# Boczek_schm_pls_check.net
KiCad netlist of a schematic drawn in EAGLE
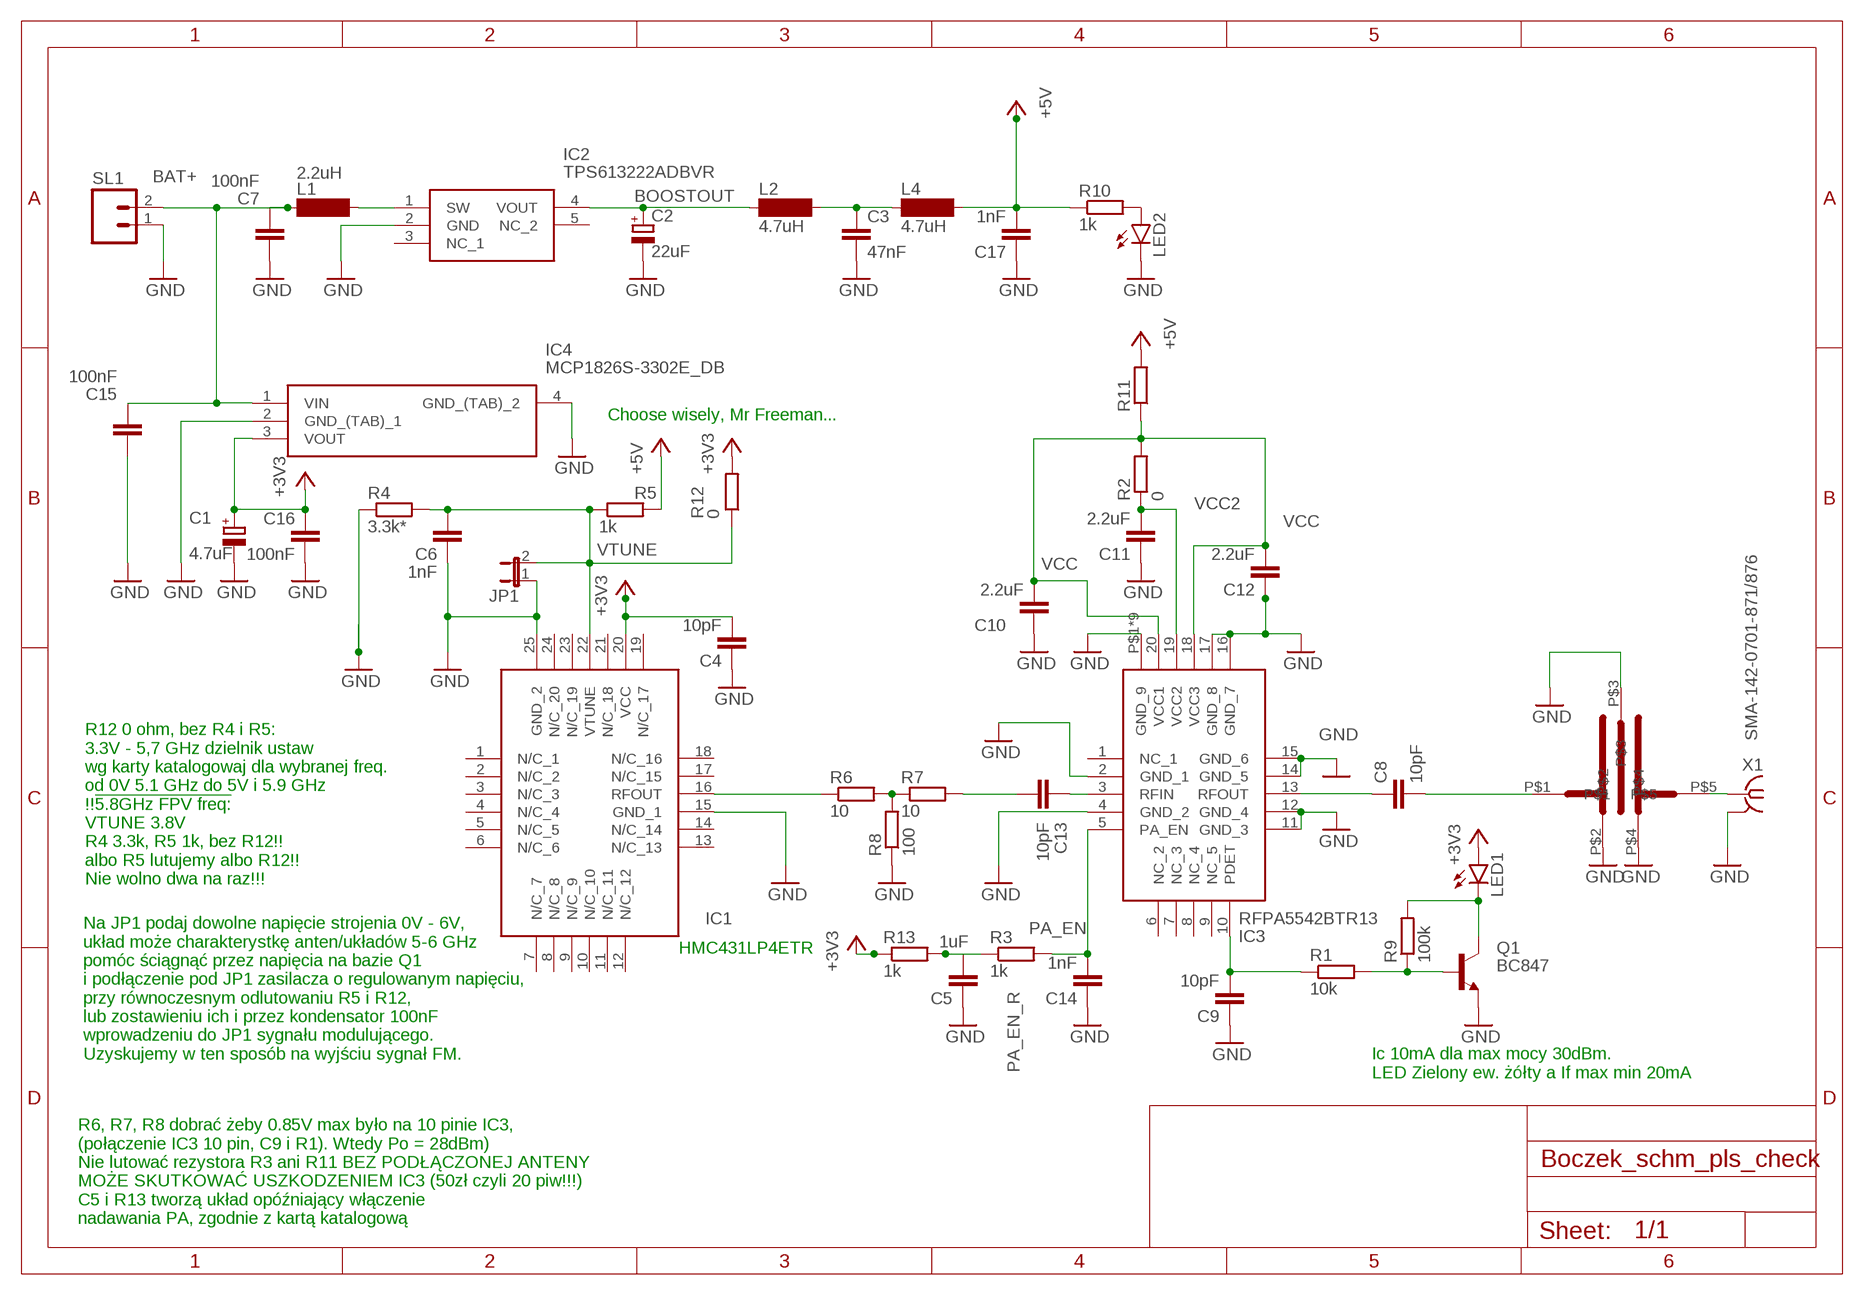
[diagram p0: schematic, sheet 1]

(export (version "E")
  (design (tool "Eeschema 10.0.6"))
  (components
    (comp (ref "C1")
      (value "4.7uF")
      (footprint "eagle-import:SMC_E")
      (libsource (lib "eagle-import") (part "CPOL-EUSMCE"))
    )
    (comp (ref "C2")
      (value "22uF")
      (footprint "eagle-import:SMC_E")
      (libsource (lib "eagle-import") (part "CPOL-EUSMCE"))
    )
    (comp (ref "C3")
      (value "47nF")
      (footprint "eagle-import:C1206")
      (libsource (lib "eagle-import") (part "C-EUC1206"))
    )
    (comp (ref "C4")
      (value "10pF")
      (footprint "eagle-import:C0603")
      (libsource (lib "eagle-import") (part "C-EUC0603"))
    )
    (comp (ref "C5")
      (value "1uF")
      (footprint "eagle-import:C1206")
      (libsource (lib "eagle-import") (part "C-EUC1206"))
    )
    (comp (ref "C6")
      (value "1nF")
      (footprint "eagle-import:C0402")
      (libsource (lib "eagle-import") (part "C-EUC0402"))
    )
    (comp (ref "C7")
      (value "100nF")
      (footprint "eagle-import:C1206")
      (libsource (lib "eagle-import") (part "C-EUC1206"))
    )
    (comp (ref "C8")
      (value "10pF")
      (footprint "eagle-import:C0402")
      (libsource (lib "eagle-import") (part "C-EUC0402"))
    )
    (comp (ref "C9")
      (value "10pF")
      (footprint "eagle-import:C0402")
      (libsource (lib "eagle-import") (part "C-EUC0402"))
    )
    (comp (ref "C10")
      (value "2.2uF")
      (footprint "eagle-import:C0402")
      (libsource (lib "eagle-import") (part "C-EUC0402"))
    )
    (comp (ref "C11")
      (value "2.2uF")
      (footprint "eagle-import:C0402")
      (libsource (lib "eagle-import") (part "C-EUC0402"))
    )
    (comp (ref "C12")
      (value "2.2uF")
      (footprint "eagle-import:C0402")
      (libsource (lib "eagle-import") (part "C-EUC0402"))
    )
    (comp (ref "C13")
      (value "10pF")
      (footprint "eagle-import:C0402")
      (libsource (lib "eagle-import") (part "C-EUC0402"))
    )
    (comp (ref "C14")
      (value "1nF")
      (footprint "eagle-import:C0402")
      (libsource (lib "eagle-import") (part "C-EUC0402"))
    )
    (comp (ref "C15")
      (value "100nF")
      (footprint "eagle-import:C1206")
      (libsource (lib "eagle-import") (part "C-EUC1206"))
    )
    (comp (ref "C16")
      (value "100nF")
      (footprint "eagle-import:C1206")
      (libsource (lib "eagle-import") (part "C-EUC1206"))
    )
    (comp (ref "C17")
      (value "1nF")
      (footprint "eagle-import:C0402")
      (libsource (lib "eagle-import") (part "C-EUC0402"))
    )
    (comp (ref "IC1")
      (value "HMC430LP4ETR")
      (footprint "eagle-import:QFN50P400X400X100-25N")
      (fields
        (field (name "MOUSER_PART_NUMBER") "584-HMC430LP4ETR")
        (field (name "MANUFACTURER_PART_NUMBER") "HMC431LP4ETR")
      )
      (libsource (lib "eagle-import") (part "HMC430LP4ETR"))
    )
    (comp (ref "IC2")
      (value "TPS613222ADBVR")
      (footprint "eagle-import:SOT95P280X145-5N")
      (fields (field (name "MOUSER_PART_NUMBER") "595-TPS613222ADBVR"))
      (libsource (lib "eagle-import") (part "TPS613222ADBVR"))
    )
    (comp (ref "IC3")
      (value "RFPA5542BTR13")
      (footprint "eagle-import:QFN50P400X400X85-21N")
      (fields (field (name "MOUSER_PART_NUMBER") "772-RFPA5542BTR13"))
      (libsource (lib "eagle-import") (part "RFPA5542BTR13"))
    )
    (comp (ref "IC4")
      (value "MCP1826S-3302E_DB")
      (footprint "eagle-import:SOT230P700X180-4N")
      (fields
        (field (name "MANUFACTURER_PART_NUMBER") "MCP1826S-3302E/DB")
        (field (name "MOUSER_PART_NUMBER") "579-MCP1826S-3302EDB")
      )
      (libsource (lib "eagle-import") (part "MCP1826S-3302E_DB"))
    )
    (comp (ref "JP1")
      (value "JP1E")
      (footprint "eagle-import:JP1")
      (libsource (lib "eagle-import") (part "JP1E"))
    )
    (comp (ref "L1")
      (value "2.2uH")
      (footprint "eagle-import:SM-NE45")
      (libsource (lib "eagle-import") (part "SM-NE45"))
    )
    (comp (ref "L2")
      (value "4.7uH")
      (footprint "eagle-import:SM-NE45")
      (fields (field (name "SPICEPREFIX") "L"))
      (libsource (lib "eagle-import") (part "SM-NE45"))
    )
    (comp (ref "L4")
      (value "4.7uH")
      (footprint "eagle-import:SM-NE45")
      (libsource (lib "eagle-import") (part "SM-NE45"))
    )
    (comp (ref "LED1")
      (value "LEDSMT1206")
      (footprint "eagle-import:1206")
      (libsource (lib "eagle-import") (part "LEDSMT1206"))
    )
    (comp (ref "LED2")
      (value "LEDSMT1206")
      (footprint "eagle-import:1206")
      (libsource (lib "eagle-import") (part "LEDSMT1206"))
    )
    (comp (ref "Q1")
      (value "BC847")
      (footprint "eagle-import:SOT23")
      (libsource (lib "eagle-import") (part "BC847"))
    )
    (comp (ref "R1")
      (value "10k")
      (footprint "eagle-import:R0603")
      (libsource (lib "eagle-import") (part "R-EU_R0603"))
    )
    (comp (ref "R2")
      (value "0")
      (footprint "eagle-import:R0603")
      (libsource (lib "eagle-import") (part "R-EU_R0603"))
    )
    (comp (ref "R3")
      (value "1k")
      (footprint "eagle-import:R0603")
      (libsource (lib "eagle-import") (part "R-EU_R0603"))
    )
    (comp (ref "R4")
      (value "3.3k*")
      (footprint "eagle-import:R0603")
      (libsource (lib "eagle-import") (part "resistor_348_R-EU_R0603"))
    )
    (comp (ref "R5")
      (value "1k")
      (footprint "eagle-import:R0603")
      (libsource (lib "eagle-import") (part "resistor_348_R-EU_R0603"))
    )
    (comp (ref "R6")
      (value "10")
      (footprint "eagle-import:R0603")
      (libsource (lib "eagle-import") (part "resistor_348_R-EU_R0603"))
    )
    (comp (ref "R7")
      (value "10")
      (footprint "eagle-import:R0603")
      (libsource (lib "eagle-import") (part "resistor_348_R-EU_R0603"))
    )
    (comp (ref "R8")
      (value "100")
      (footprint "eagle-import:R0603")
      (libsource (lib "eagle-import") (part "resistor_348_R-EU_R0603"))
    )
    (comp (ref "R9")
      (value "100k")
      (footprint "eagle-import:R0603")
      (libsource (lib "eagle-import") (part "resistor_348_R-EU_R0603"))
    )
    (comp (ref "R10")
      (value "1k")
      (footprint "eagle-import:R0603")
      (libsource (lib "eagle-import") (part "R-EU_R0603"))
    )
    (comp (ref "R11")
      (value "0")
      (footprint "eagle-import:R0603")
      (libsource (lib "eagle-import") (part "R-EU_R0603"))
    )
    (comp (ref "R12")
      (value "0")
      (footprint "eagle-import:R0603")
      (libsource (lib "eagle-import") (part "R-EU_R0603"))
    )
    (comp (ref "R13")
      (value "1k")
      (footprint "eagle-import:R0603")
      (libsource (lib "eagle-import") (part "R-EU_R0603"))
    )
    (comp (ref "SL1")
      (value "M02")
      (footprint "eagle-import:02P")
      (libsource (lib "eagle-import") (part "M02"))
    )
    (comp (ref "U$1")
      (value "INTERDIGITAL_FILTER_3RD_ORDER")
      (footprint "eagle-import:JLC7628_5000_6000_3RDORDER_FILTER")
      (libsource (lib "eagle-import") (part "INTERDIGITAL_FILTER_3RD_ORDER"))
    )
    (comp (ref "X1")
      (value "SMA-142-0701-871/876")
      (footprint "eagle-import:J502-ND-142-0701-871_876")
      (fields (field (name "MF") "JOHNSON COMPONENTS") (field (name "MPN") "142-0701-871"))
      (libsource (lib "eagle-import") (part "SMA-142-0701-871/876"))
    )
  )
  (nets
    (net (code "1") (name "+3V3") (class "Default")
      (node (ref "C1") (pin "+") (pinfunction "+_+") (pintype "passive"))
      (node (ref "C16") (pin "2") (pinfunction "2_2") (pintype "passive"))
      (node (ref "C4") (pin "2") (pinfunction "2_2") (pintype "passive"))
      (node (ref "IC1") (pin "20") (pinfunction "VCC_20") (pintype "bidirectional"))
      (node (ref "IC4") (pin "3") (pinfunction "VOUT_3") (pintype "bidirectional"))
      (node (ref "LED1") (pin "A") (pinfunction "A_A") (pintype "passive"))
      (node (ref "R12") (pin "2") (pinfunction "2_2") (pintype "passive"))
      (node (ref "R13") (pin "1") (pinfunction "1_1") (pintype "passive"))
    )
    (net (code "2") (name "+5V") (class "Default")
      (node (ref "C17") (pin "2") (pinfunction "2_2") (pintype "passive"))
      (node (ref "L4") (pin "2") (pinfunction "2_2") (pintype "passive"))
      (node (ref "R10") (pin "1") (pinfunction "1_1") (pintype "passive"))
      (node (ref "R11") (pin "2") (pinfunction "2_2") (pintype "passive"))
      (node (ref "R5") (pin "2") (pinfunction "2_2") (pintype "passive"))
    )
    (net (code "3") (name "/BAT+") (class "Default")
      (node (ref "C15") (pin "2") (pinfunction "2_2") (pintype "passive"))
      (node (ref "C7") (pin "2") (pinfunction "2_2") (pintype "passive"))
      (node (ref "IC4") (pin "1") (pinfunction "VIN_1") (pintype "bidirectional"))
      (node (ref "L1") (pin "1") (pinfunction "1_1") (pintype "passive"))
      (node (ref "SL1") (pin "2") (pinfunction "2_2") (pintype "passive"))
    )
    (net (code "4") (name "/BOOSTOUT") (class "Default")
      (node (ref "C2") (pin "+") (pinfunction "+_+") (pintype "passive"))
      (node (ref "IC2") (pin "4") (pinfunction "VOUT_4") (pintype "bidirectional"))
      (node (ref "L2") (pin "1") (pinfunction "1_1") (pintype "passive"))
    )
    (net (code "5") (name "/PA_EN") (class "Default")
      (node (ref "C14") (pin "2") (pinfunction "2_2") (pintype "passive"))
      (node (ref "IC3") (pin "5") (pinfunction "PA_EN_5") (pintype "bidirectional"))
      (node (ref "R3") (pin "2") (pinfunction "2_2") (pintype "passive"))
    )
    (net (code "6") (name "/PA_EN_R") (class "Default")
      (node (ref "C5") (pin "2") (pinfunction "2_2") (pintype "passive"))
      (node (ref "R13") (pin "2") (pinfunction "2_2") (pintype "passive"))
      (node (ref "R3") (pin "1") (pinfunction "1_1") (pintype "passive"))
    )
    (net (code "7") (name "/VCC") (class "Default")
      (node (ref "C10") (pin "2") (pinfunction "2_2") (pintype "passive"))
      (node (ref "C12") (pin "2") (pinfunction "2_2") (pintype "passive"))
      (node (ref "IC3") (pin "18") (pinfunction "VCC3_18") (pintype "bidirectional"))
      (node (ref "IC3") (pin "20") (pinfunction "VCC1_20") (pintype "bidirectional"))
      (node (ref "R11") (pin "1") (pinfunction "1_1") (pintype "passive"))
      (node (ref "R2") (pin "2") (pinfunction "2_2") (pintype "passive"))
    )
    (net (code "8") (name "/VCC2") (class "Default")
      (node (ref "C11") (pin "2") (pinfunction "2_2") (pintype "passive"))
      (node (ref "IC3") (pin "19") (pinfunction "VCC2_19") (pintype "bidirectional"))
      (node (ref "R2") (pin "1") (pinfunction "1_1") (pintype "passive"))
    )
    (net (code "9") (name "/VTUNE") (class "Default")
      (node (ref "C6") (pin "2") (pinfunction "2_2") (pintype "passive"))
      (node (ref "IC1") (pin "22") (pinfunction "VTUNE_22") (pintype "bidirectional"))
      (node (ref "JP1") (pin "2") (pinfunction "2_2") (pintype "passive"))
      (node (ref "R12") (pin "1") (pinfunction "1_1") (pintype "passive"))
      (node (ref "R4") (pin "2") (pinfunction "2_2") (pintype "passive"))
      (node (ref "R5") (pin "1") (pinfunction "1_1") (pintype "passive"))
    )
    (net (code "10") (name "GND") (class "Default")
      (node (ref "C1") (pin "-") (pinfunction "-_-") (pintype "passive"))
      (node (ref "C10") (pin "1") (pinfunction "1_1") (pintype "passive"))
      (node (ref "C11") (pin "1") (pinfunction "1_1") (pintype "passive"))
      (node (ref "C12") (pin "1") (pinfunction "1_1") (pintype "passive"))
      (node (ref "C14") (pin "1") (pinfunction "1_1") (pintype "passive"))
      (node (ref "C15") (pin "1") (pinfunction "1_1") (pintype "passive"))
      (node (ref "C16") (pin "1") (pinfunction "1_1") (pintype "passive"))
      (node (ref "C17") (pin "1") (pinfunction "1_1") (pintype "passive"))
      (node (ref "C2") (pin "-") (pinfunction "-_-") (pintype "passive"))
      (node (ref "C3") (pin "2") (pinfunction "2_2") (pintype "passive"))
      (node (ref "C4") (pin "1") (pinfunction "1_1") (pintype "passive"))
      (node (ref "C5") (pin "1") (pinfunction "1_1") (pintype "passive"))
      (node (ref "C6") (pin "1") (pinfunction "1_1") (pintype "passive"))
      (node (ref "C7") (pin "1") (pinfunction "1_1") (pintype "passive"))
      (node (ref "C9") (pin "1") (pinfunction "1_1") (pintype "passive"))
      (node (ref "IC1") (pin "15") (pinfunction "GND_1_15") (pintype "bidirectional"))
      (node (ref "IC1") (pin "25") (pinfunction "GND_2_25") (pintype "bidirectional"))
      (node (ref "IC2") (pin "2") (pinfunction "GND_2") (pintype "bidirectional"))
      (node (ref "IC3") (pin "11") (pinfunction "GND_3_11") (pintype "bidirectional"))
      (node (ref "IC3") (pin "12") (pinfunction "GND_4_12") (pintype "bidirectional"))
      (node (ref "IC3") (pin "14") (pinfunction "GND_5_14") (pintype "bidirectional"))
      (node (ref "IC3") (pin "15") (pinfunction "GND_6_15") (pintype "bidirectional"))
      (node (ref "IC3") (pin "16") (pinfunction "GND_7_16") (pintype "bidirectional"))
      (node (ref "IC3") (pin "17") (pinfunction "GND_8_17") (pintype "bidirectional"))
      (node (ref "IC3") (pin "2") (pinfunction "GND_1_2") (pintype "bidirectional"))
      (node (ref "IC3") (pin "4") (pinfunction "GND_2_4") (pintype "bidirectional"))
      (node (ref "IC3") (pin "P$1") (pinfunction "GND_9_P$1") (pintype "bidirectional"))
      (node (ref "IC3") (pin "P$2") (pinfunction "GND_9_P$2") (pintype "bidirectional"))
      (node (ref "IC3") (pin "P$3") (pinfunction "GND_9_P$3") (pintype "bidirectional"))
      (node (ref "IC3") (pin "P$4") (pinfunction "GND_9_P$4") (pintype "bidirectional"))
      (node (ref "IC3") (pin "P$5") (pinfunction "GND_9_P$5") (pintype "bidirectional"))
      (node (ref "IC3") (pin "P$6") (pinfunction "GND_9_P$6") (pintype "bidirectional"))
      (node (ref "IC3") (pin "P$7") (pinfunction "GND_9_P$7") (pintype "bidirectional"))
      (node (ref "IC3") (pin "P$8") (pinfunction "GND_9_P$8") (pintype "bidirectional"))
      (node (ref "IC3") (pin "P$9") (pinfunction "GND_9_P$9") (pintype "bidirectional"))
      (node (ref "IC4") (pin "2") (pinfunction "GND_(TAB)_1_2") (pintype "bidirectional"))
      (node (ref "IC4") (pin "4") (pinfunction "GND_(TAB)_2_4") (pintype "bidirectional"))
      (node (ref "JP1") (pin "1") (pinfunction "1_1") (pintype "passive"))
      (node (ref "LED2") (pin "C") (pinfunction "C_C") (pintype "passive"))
      (node (ref "Q1") (pin "2") (pinfunction "E_2") (pintype "passive"))
      (node (ref "R4") (pin "1") (pinfunction "1_1") (pintype "passive"))
      (node (ref "R8") (pin "1") (pinfunction "1_1") (pintype "passive"))
      (node (ref "SL1") (pin "1") (pinfunction "1_1") (pintype "passive"))
      (node (ref "U$1") (pin "P$2") (pinfunction "P$2_P$2") (pintype "bidirectional"))
      (node (ref "U$1") (pin "P$3") (pinfunction "P$3_P$3") (pintype "bidirectional"))
      (node (ref "U$1") (pin "P$4") (pinfunction "P$4_P$4") (pintype "bidirectional"))
      (node (ref "X1") (pin "G@1") (pinfunction "2_G@1") (pintype "passive"))
      (node (ref "X1") (pin "G@2") (pinfunction "2_G@2") (pintype "passive"))
      (node (ref "X1") (pin "G@3") (pinfunction "2_G@3") (pintype "passive"))
      (node (ref "X1") (pin "G@4") (pinfunction "2_G@4") (pintype "passive"))
    )
    (net (code "11") (name "Net-(C3-Pad1)") (class "Default")
      (node (ref "C3") (pin "1") (pinfunction "1_1") (pintype "passive"))
      (node (ref "L2") (pin "2") (pinfunction "2_2") (pintype "passive"))
      (node (ref "L4") (pin "1") (pinfunction "1_1") (pintype "passive"))
    )
    (net (code "12") (name "Net-(C8-Pad2)") (class "Default")
      (node (ref "C8") (pin "2") (pinfunction "2_2") (pintype "passive"))
      (node (ref "U$1") (pin "P$1") (pinfunction "P$1_P$1") (pintype "bidirectional"))
    )
    (net (code "13") (name "Net-(C13-Pad2)") (class "Default")
      (node (ref "C13") (pin "2") (pinfunction "2_2") (pintype "passive"))
      (node (ref "R7") (pin "2") (pinfunction "2_2") (pintype "passive"))
    )
    (net (code "14") (name "Net-(IC1-RFOUT)") (class "Default")
      (node (ref "IC1") (pin "16") (pinfunction "RFOUT_16") (pintype "bidirectional"))
      (node (ref "R6") (pin "1") (pinfunction "1_1") (pintype "passive"))
    )
    (net (code "15") (name "Net-(IC2-SW)") (class "Default")
      (node (ref "IC2") (pin "1") (pinfunction "SW_1") (pintype "bidirectional"))
      (node (ref "L1") (pin "2") (pinfunction "2_2") (pintype "passive"))
    )
    (net (code "16") (name "Net-(IC3-PDET)") (class "Default")
      (node (ref "C9") (pin "2") (pinfunction "2_2") (pintype "passive"))
      (node (ref "IC3") (pin "10") (pinfunction "PDET_10") (pintype "bidirectional"))
      (node (ref "R1") (pin "1") (pinfunction "1_1") (pintype "passive"))
    )
    (net (code "17") (name "Net-(IC3-RFIN)") (class "Default")
      (node (ref "C13") (pin "1") (pinfunction "1_1") (pintype "passive"))
      (node (ref "IC3") (pin "3") (pinfunction "RFIN_3") (pintype "bidirectional"))
    )
    (net (code "18") (name "Net-(IC3-RFOUT)") (class "Default")
      (node (ref "C8") (pin "1") (pinfunction "1_1") (pintype "passive"))
      (node (ref "IC3") (pin "13") (pinfunction "RFOUT_13") (pintype "bidirectional"))
    )
    (net (code "19") (name "Net-(LED2-PadA)") (class "Default")
      (node (ref "LED2") (pin "A") (pinfunction "A_A") (pintype "passive"))
      (node (ref "R10") (pin "2") (pinfunction "2_2") (pintype "passive"))
    )
    (net (code "20") (name "Net-(Q1-B)") (class "Default")
      (node (ref "Q1") (pin "1") (pinfunction "B_1") (pintype "passive"))
      (node (ref "R1") (pin "2") (pinfunction "2_2") (pintype "passive"))
      (node (ref "R9") (pin "1") (pinfunction "1_1") (pintype "passive"))
    )
    (net (code "21") (name "Net-(Q1-C)") (class "Default")
      (node (ref "LED1") (pin "C") (pinfunction "C_C") (pintype "passive"))
      (node (ref "Q1") (pin "3") (pinfunction "C_3") (pintype "passive"))
      (node (ref "R9") (pin "2") (pinfunction "2_2") (pintype "passive"))
    )
    (net (code "22") (name "Net-(R6-Pad2)") (class "Default")
      (node (ref "R6") (pin "2") (pinfunction "2_2") (pintype "passive"))
      (node (ref "R7") (pin "1") (pinfunction "1_1") (pintype "passive"))
      (node (ref "R8") (pin "2") (pinfunction "2_2") (pintype "passive"))
    )
    (net (code "23") (name "Net-(U$1-PadP$5)") (class "Default")
      (node (ref "U$1") (pin "P$5") (pinfunction "P$5_P$5") (pintype "bidirectional"))
      (node (ref "X1") (pin "1") (pinfunction "1_1") (pintype "passive"))
    )
    (net (code "24") (name "unconnected-(IC1-N{slash}C_1-Pad1)") (class "Default")
      (node (ref "IC1") (pin "1") (pinfunction "N/C_1_1") (pintype "bidirectional"))
    )
    (net (code "25") (name "unconnected-(IC1-N{slash}C_2-Pad2)") (class "Default")
      (node (ref "IC1") (pin "2") (pinfunction "N/C_2_2") (pintype "bidirectional"))
    )
    (net (code "26") (name "unconnected-(IC1-N{slash}C_3-Pad3)") (class "Default")
      (node (ref "IC1") (pin "3") (pinfunction "N/C_3_3") (pintype "bidirectional"))
    )
    (net (code "27") (name "unconnected-(IC1-N{slash}C_4-Pad4)") (class "Default")
      (node (ref "IC1") (pin "4") (pinfunction "N/C_4_4") (pintype "bidirectional"))
    )
    (net (code "28") (name "unconnected-(IC1-N{slash}C_5-Pad5)") (class "Default")
      (node (ref "IC1") (pin "5") (pinfunction "N/C_5_5") (pintype "bidirectional"))
    )
    (net (code "29") (name "unconnected-(IC1-N{slash}C_6-Pad6)") (class "Default")
      (node (ref "IC1") (pin "6") (pinfunction "N/C_6_6") (pintype "bidirectional"))
    )
    (net (code "30") (name "unconnected-(IC1-N{slash}C_7-Pad7)") (class "Default")
      (node (ref "IC1") (pin "7") (pinfunction "N/C_7_7") (pintype "bidirectional"))
    )
    (net (code "31") (name "unconnected-(IC1-N{slash}C_8-Pad8)") (class "Default")
      (node (ref "IC1") (pin "8") (pinfunction "N/C_8_8") (pintype "bidirectional"))
    )
    (net (code "32") (name "unconnected-(IC1-N{slash}C_9-Pad9)") (class "Default")
      (node (ref "IC1") (pin "9") (pinfunction "N/C_9_9") (pintype "bidirectional"))
    )
    (net (code "33") (name "unconnected-(IC1-N{slash}C_10-Pad10)") (class "Default")
      (node (ref "IC1") (pin "10") (pinfunction "N/C_10_10") (pintype "bidirectional"))
    )
    (net (code "34") (name "unconnected-(IC1-N{slash}C_11-Pad11)") (class "Default")
      (node (ref "IC1") (pin "11") (pinfunction "N/C_11_11") (pintype "bidirectional"))
    )
    (net (code "35") (name "unconnected-(IC1-N{slash}C_12-Pad12)") (class "Default")
      (node (ref "IC1") (pin "12") (pinfunction "N/C_12_12") (pintype "bidirectional"))
    )
    (net (code "36") (name "unconnected-(IC1-N{slash}C_13-Pad13)") (class "Default")
      (node (ref "IC1") (pin "13") (pinfunction "N/C_13_13") (pintype "bidirectional"))
    )
    (net (code "37") (name "unconnected-(IC1-N{slash}C_14-Pad14)") (class "Default")
      (node (ref "IC1") (pin "14") (pinfunction "N/C_14_14") (pintype "bidirectional"))
    )
    (net (code "38") (name "unconnected-(IC1-N{slash}C_15-Pad17)") (class "Default")
      (node (ref "IC1") (pin "17") (pinfunction "N/C_15_17") (pintype "bidirectional"))
    )
    (net (code "39") (name "unconnected-(IC1-N{slash}C_16-Pad18)") (class "Default")
      (node (ref "IC1") (pin "18") (pinfunction "N/C_16_18") (pintype "bidirectional"))
    )
    (net (code "40") (name "unconnected-(IC1-N{slash}C_17-Pad19)") (class "Default")
      (node (ref "IC1") (pin "19") (pinfunction "N/C_17_19") (pintype "bidirectional"))
    )
    (net (code "41") (name "unconnected-(IC1-N{slash}C_18-Pad21)") (class "Default")
      (node (ref "IC1") (pin "21") (pinfunction "N/C_18_21") (pintype "bidirectional"))
    )
    (net (code "42") (name "unconnected-(IC1-N{slash}C_19-Pad23)") (class "Default")
      (node (ref "IC1") (pin "23") (pinfunction "N/C_19_23") (pintype "bidirectional"))
    )
    (net (code "43") (name "unconnected-(IC1-N{slash}C_20-Pad24)") (class "Default")
      (node (ref "IC1") (pin "24") (pinfunction "N/C_20_24") (pintype "bidirectional"))
    )
    (net (code "44") (name "unconnected-(IC2-NC_1-Pad3)") (class "Default")
      (node (ref "IC2") (pin "3") (pinfunction "NC_1_3") (pintype "bidirectional"))
    )
    (net (code "45") (name "unconnected-(IC2-NC_2-Pad5)") (class "Default")
      (node (ref "IC2") (pin "5") (pinfunction "NC_2_5") (pintype "bidirectional"))
    )
    (net (code "46") (name "unconnected-(IC3-NC_1-Pad1)") (class "Default")
      (node (ref "IC3") (pin "1") (pinfunction "NC_1_1") (pintype "bidirectional"))
    )
    (net (code "47") (name "unconnected-(IC3-NC_2-Pad6)") (class "Default")
      (node (ref "IC3") (pin "6") (pinfunction "NC_2_6") (pintype "bidirectional"))
    )
    (net (code "48") (name "unconnected-(IC3-NC_3-Pad7)") (class "Default")
      (node (ref "IC3") (pin "7") (pinfunction "NC_3_7") (pintype "bidirectional"))
    )
    (net (code "49") (name "unconnected-(IC3-NC_4-Pad8)") (class "Default")
      (node (ref "IC3") (pin "8") (pinfunction "NC_4_8") (pintype "bidirectional"))
    )
    (net (code "50") (name "unconnected-(IC3-NC_5-Pad9)") (class "Default")
      (node (ref "IC3") (pin "9") (pinfunction "NC_5_9") (pintype "bidirectional"))
    )
  )
)
